# 2.net
KiCad netlist of a schematic drawn in Altium Designer
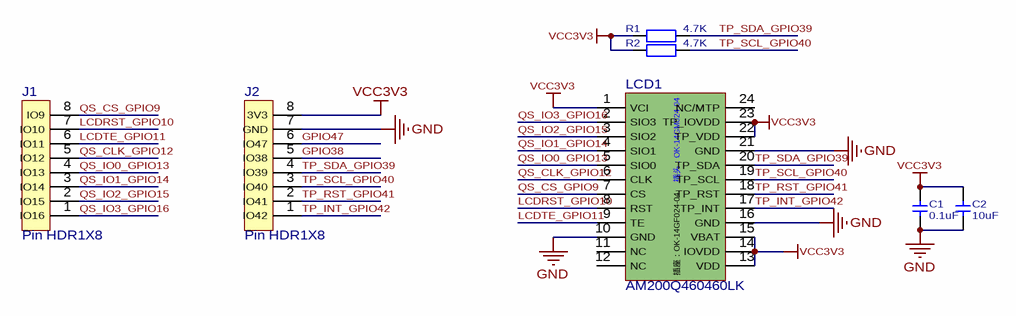
[diagram p0: 2寸屏幕转接板.SchDoc]

(export (version "E")
  (design (tool "Eeschema 10.0.6"))
  (components
    (comp (ref "C1")
      (value "0.1uF")
      (footprint "CAP_0402 - G")
      (description "Capacitor")
      (libsource (lib "ODG_AD_Lib") (part "CAP"))
    )
    (comp (ref "C2")
      (value "10uF")
      (footprint "CAP_0402 - G")
      (description "Capacitor")
      (libsource (lib "ODG_AD_Lib") (part "CAP"))
    )
    (comp (ref "J1")
      (value "Pin HDR1X8")
      (footprint "HDR-SMD_8P-P2.54-V-M-LS4.8_XKB_R1")
      (libsource (lib "排针") (part "Pin HDR1X8"))
    )
    (comp (ref "J2")
      (value "Pin HDR1X8")
      (footprint "HDR-SMD_8P-P2.54-V-M-LS4.8_XKB_R1")
      (libsource (lib "排针") (part "Pin HDR1X8"))
    )
    (comp (ref "LCD1")
      (value "AM200Q460460LK")
      (footprint "2寸AMOLED")
      (description "2.0寸AMOLED 460*460")
      (libsource (lib "RV1106G3开发板") (part "AM200Q460460LK"))
    )
    (comp (ref "R1")
      (value "4.7K")
      (footprint "RES_0402 -G")
      (description "Resistor")
      (fields (field (name "PUBLISHER") "*"))
      (libsource (lib "*") (part "Res2"))
    )
    (comp (ref "R2")
      (value "4.7K")
      (footprint "RES_0402 -G")
      (description "Resistor")
      (fields (field (name "PUBLISHER") "*"))
      (libsource (lib "*") (part "Res2"))
    )
  )
  (nets
    (net (code "1") (name "/GPIO38") (class "Default")
      (node (ref "J2") (pin "5") (pinfunction "IO38_5") (pintype "passive"))
    )
    (net (code "2") (name "/GPIO47") (class "Default")
      (node (ref "J2") (pin "6") (pinfunction "IO47_6") (pintype "passive"))
    )
    (net (code "3") (name "/LCDRST_GPIO10") (class "Default")
      (node (ref "J1") (pin "7") (pinfunction "GND_7") (pintype "passive"))
      (node (ref "LCD1") (pin "8") (pinfunction "RST_8") (pintype "passive"))
    )
    (net (code "4") (name "/LCDTE_GPIO11") (class "Default")
      (node (ref "J1") (pin "6") (pinfunction "IO47_6") (pintype "passive"))
      (node (ref "LCD1") (pin "9") (pinfunction "TE_9") (pintype "passive"))
    )
    (net (code "5") (name "/QS_CLK_GPIO12") (class "Default")
      (node (ref "J1") (pin "5") (pinfunction "IO38_5") (pintype "passive"))
      (node (ref "LCD1") (pin "6") (pinfunction "CLK_6") (pintype "passive"))
    )
    (net (code "6") (name "/QS_CS_GPIO9") (class "Default")
      (node (ref "J1") (pin "8") (pinfunction "3V3_8") (pintype "passive"))
      (node (ref "LCD1") (pin "7") (pinfunction "CS_7") (pintype "passive"))
    )
    (net (code "7") (name "/QS_IO0_GPIO13") (class "Default")
      (node (ref "J1") (pin "4") (pinfunction "IO39_4") (pintype "passive"))
      (node (ref "LCD1") (pin "5") (pinfunction "SIO0_5") (pintype "passive"))
    )
    (net (code "8") (name "/QS_IO1_GPIO14") (class "Default")
      (node (ref "J1") (pin "3") (pinfunction "IO40_3") (pintype "passive"))
      (node (ref "LCD1") (pin "4") (pinfunction "SIO1_4") (pintype "passive"))
    )
    (net (code "9") (name "/QS_IO2_GPIO15") (class "Default")
      (node (ref "J1") (pin "2") (pinfunction "IO41_2") (pintype "passive"))
      (node (ref "LCD1") (pin "3") (pinfunction "SIO2_3") (pintype "passive"))
    )
    (net (code "10") (name "/QS_IO3_GPIO16") (class "Default")
      (node (ref "J1") (pin "1") (pinfunction "IO42_1") (pintype "passive"))
      (node (ref "LCD1") (pin "2") (pinfunction "SIO3_2") (pintype "passive"))
    )
    (net (code "11") (name "/TP_INT_GPIO42") (class "Default")
      (node (ref "J2") (pin "1") (pinfunction "IO42_1") (pintype "passive"))
      (node (ref "LCD1") (pin "17") (pinfunction "TP_INT_17") (pintype "passive"))
    )
    (net (code "12") (name "/TP_RST_GPIO41") (class "Default")
      (node (ref "J2") (pin "2") (pinfunction "IO41_2") (pintype "passive"))
      (node (ref "LCD1") (pin "18") (pinfunction "TP_RST_18") (pintype "passive"))
    )
    (net (code "13") (name "/TP_SCL_GPIO40") (class "Default")
      (node (ref "J2") (pin "3") (pinfunction "IO40_3") (pintype "passive"))
      (node (ref "LCD1") (pin "19") (pinfunction "TP_SCL_19") (pintype "passive"))
      (node (ref "R2") (pin "1") (pinfunction "1_1") (pintype "passive"))
    )
    (net (code "14") (name "/TP_SDA_GPIO39") (class "Default")
      (node (ref "J2") (pin "4") (pinfunction "IO39_4") (pintype "passive"))
      (node (ref "LCD1") (pin "20") (pinfunction "TP_SDA_20") (pintype "passive"))
      (node (ref "R1") (pin "1") (pinfunction "1_1") (pintype "passive"))
    )
    (net (code "15") (name "GND") (class "Default")
      (node (ref "C1") (pin "2") (pinfunction "2_2") (pintype "passive"))
      (node (ref "C2") (pin "2") (pinfunction "2_2") (pintype "passive"))
      (node (ref "J2") (pin "7") (pinfunction "GND_7") (pintype "passive"))
      (node (ref "LCD1") (pin "10") (pinfunction "GND_10") (pintype "passive"))
      (node (ref "LCD1") (pin "16") (pinfunction "GND_16") (pintype "passive"))
      (node (ref "LCD1") (pin "21") (pinfunction "GND_21") (pintype "passive"))
    )
    (net (code "16") (name "VCC3V3") (class "Default")
      (node (ref "C1") (pin "1") (pinfunction "1_1") (pintype "passive"))
      (node (ref "C2") (pin "1") (pinfunction "1_1") (pintype "passive"))
      (node (ref "J2") (pin "8") (pinfunction "3V3_8") (pintype "passive"))
      (node (ref "LCD1") (pin "1") (pinfunction "VCI_1") (pintype "passive"))
      (node (ref "LCD1") (pin "13") (pinfunction "VDD_13") (pintype "passive"))
      (node (ref "LCD1") (pin "14") (pinfunction "IOVDD_14") (pintype "passive"))
      (node (ref "LCD1") (pin "15") (pinfunction "VBAT_15") (pintype "passive"))
      (node (ref "LCD1") (pin "22") (pinfunction "TP_VDD_22") (pintype "passive"))
      (node (ref "LCD1") (pin "23") (pinfunction "TP_IOVDD_23") (pintype "passive"))
      (node (ref "R1") (pin "2") (pinfunction "2_2") (pintype "passive"))
      (node (ref "R2") (pin "2") (pinfunction "2_2") (pintype "passive"))
    )
    (net (code "17") (name "unconnected-(LCD1-NC-Pad11)") (class "Default")
      (node (ref "LCD1") (pin "11") (pinfunction "NC_11") (pintype "passive"))
    )
    (net (code "18") (name "unconnected-(LCD1-NC-Pad12)") (class "Default")
      (node (ref "LCD1") (pin "12") (pinfunction "NC_12") (pintype "passive"))
    )
    (net (code "19") (name "unconnected-(LCD1-NC{slash}MTP-Pad24)") (class "Default")
      (node (ref "LCD1") (pin "24") (pinfunction "NC/MTP_24") (pintype "passive"))
    )
  )
)
